# projek_flipflop.net
KiCad netlist of a schematic drawn in EAGLE
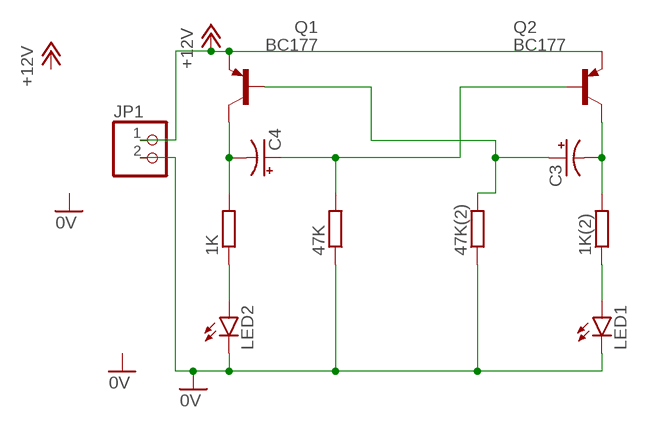
[diagram p0: schematic, sheet 1]

(export (version "E")
  (design (tool "Eeschema 10.0.6"))
  (components
    (comp (ref "1K")
      (value "R-EU_0207/15")
      (footprint "eagle-import:0207_15")
      (libsource (lib "eagle-import") (part "R-EU_0207/15"))
    )
    (comp (ref "1K(2)")
      (value "R-EU_0207/15")
      (footprint "eagle-import:0207_15")
      (libsource (lib "eagle-import") (part "R-EU_0207/15"))
    )
    (comp (ref "47K")
      (value "R-EU_0207/15")
      (footprint "eagle-import:0207_15")
      (libsource (lib "eagle-import") (part "R-EU_0207/15"))
    )
    (comp (ref "47K(2)")
      (value "R-EU_0207/15")
      (footprint "eagle-import:0207_15")
      (libsource (lib "eagle-import") (part "R-EU_0207/15"))
    )
    (comp (ref "C3")
      (value "CPOL-USE2.5-5")
      (footprint "eagle-import:E2,5-5")
      (libsource (lib "eagle-import") (part "CPOL-USE2.5-5"))
    )
    (comp (ref "C4")
      (value "CPOL-USE2.5-5")
      (footprint "eagle-import:E2,5-5")
      (libsource (lib "eagle-import") (part "CPOL-USE2.5-5"))
    )
    (comp (ref "JP1")
      (value "PINHD-1X2")
      (footprint "eagle-import:1X02")
      (libsource (lib "eagle-import") (part "PINHD-1X2"))
    )
    (comp (ref "LED1")
      (value "LED5MM")
      (footprint "eagle-import:LED5MM")
      (libsource (lib "eagle-import") (part "LED5MM"))
    )
    (comp (ref "LED2")
      (value "LED5MM")
      (footprint "eagle-import:LED5MM")
      (libsource (lib "eagle-import") (part "LED5MM"))
    )
    (comp (ref "Q1")
      (value "BC177")
      (footprint "eagle-import:TO18")
      (libsource (lib "eagle-import") (part "BC177"))
    )
    (comp (ref "Q2")
      (value "BC177")
      (footprint "eagle-import:TO18")
      (libsource (lib "eagle-import") (part "BC177"))
    )
  )
  (nets
    (net (code "1") (name "+12V") (class "Default")
      (node (ref "JP1") (pin "1") (pinfunction "1_1") (pintype "passive"))
      (node (ref "Q1") (pin "1") (pinfunction "E_1") (pintype "passive"))
      (node (ref "Q2") (pin "1") (pinfunction "E_1") (pintype "passive"))
    )
    (net (code "2") (name "0V") (class "Default")
      (node (ref "47K") (pin "1") (pinfunction "1_1") (pintype "passive"))
      (node (ref "47K(2)") (pin "1") (pinfunction "1_1") (pintype "passive"))
      (node (ref "JP1") (pin "2") (pinfunction "2_2") (pintype "passive"))
      (node (ref "LED1") (pin "K") (pinfunction "C_K") (pintype "passive"))
      (node (ref "LED2") (pin "K") (pinfunction "C_K") (pintype "passive"))
    )
    (net (code "3") (name "Net-(1K(2)-Pad1)") (class "Default")
      (node (ref "1K(2)") (pin "1") (pinfunction "1_1") (pintype "passive"))
      (node (ref "LED1") (pin "A") (pinfunction "A_A") (pintype "passive"))
    )
    (net (code "4") (name "Net-(1K-Pad1)") (class "Default")
      (node (ref "1K") (pin "1") (pinfunction "1_1") (pintype "passive"))
      (node (ref "LED2") (pin "A") (pinfunction "A_A") (pintype "passive"))
    )
    (net (code "5") (name "Net-(Q1-B)") (class "Default")
      (node (ref "47K(2)") (pin "2") (pinfunction "2_2") (pintype "passive"))
      (node (ref "C3") (pin "+") (pinfunction "+_+") (pintype "passive"))
      (node (ref "Q1") (pin "2") (pinfunction "B_2") (pintype "passive"))
    )
    (net (code "6") (name "Net-(Q1-C)") (class "Default")
      (node (ref "1K") (pin "2") (pinfunction "2_2") (pintype "passive"))
      (node (ref "C4") (pin "-") (pinfunction "-_-") (pintype "passive"))
      (node (ref "Q1") (pin "3") (pinfunction "C_3") (pintype "passive"))
    )
    (net (code "7") (name "Net-(Q2-B)") (class "Default")
      (node (ref "47K") (pin "2") (pinfunction "2_2") (pintype "passive"))
      (node (ref "C4") (pin "+") (pinfunction "+_+") (pintype "passive"))
      (node (ref "Q2") (pin "2") (pinfunction "B_2") (pintype "passive"))
    )
    (net (code "8") (name "Net-(Q2-C)") (class "Default")
      (node (ref "1K(2)") (pin "2") (pinfunction "2_2") (pintype "passive"))
      (node (ref "C3") (pin "-") (pinfunction "-_-") (pintype "passive"))
      (node (ref "Q2") (pin "3") (pinfunction "C_3") (pintype "passive"))
    )
  )
)
